# 5servoBreakoutSchematic.net
KiCad netlist of a schematic drawn in EAGLE
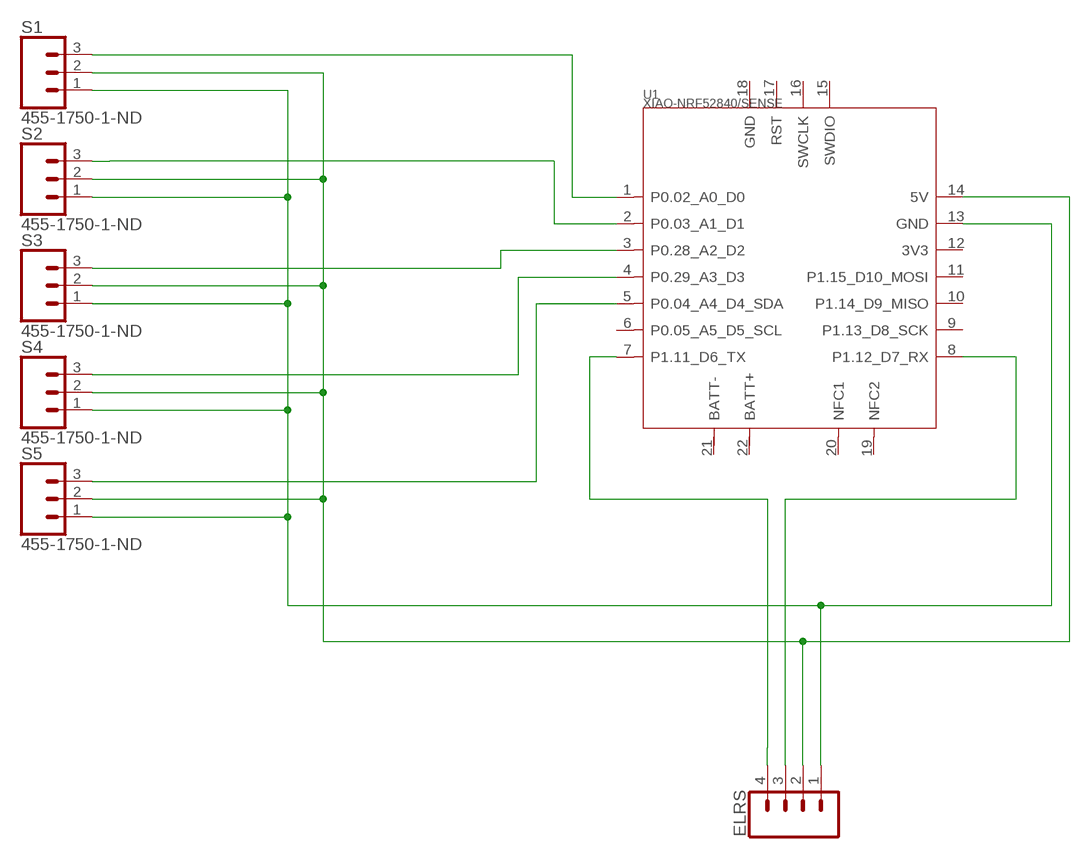
[diagram p0: schematic, sheet 1]

(export (version "E")
  (design (tool "Eeschema 10.0.6"))
  (components
    (comp (ref "ELRS")
      (value "CONN_04PTH")
      (footprint "eagle-import:1X04")
      (libsource (lib "eagle-import") (part "CONN_04PTH"))
    )
    (comp (ref "S1")
      (value "455-1750-1-ND")
      (footprint "eagle-import:1X03")
      (libsource (lib "eagle-import") (part "CONN_03"))
    )
    (comp (ref "S2")
      (value "455-1750-1-ND")
      (footprint "eagle-import:1X03")
      (libsource (lib "eagle-import") (part "CONN_03"))
    )
    (comp (ref "S3")
      (value "455-1750-1-ND")
      (footprint "eagle-import:1X03")
      (libsource (lib "eagle-import") (part "CONN_03"))
    )
    (comp (ref "S4")
      (value "455-1750-1-ND")
      (footprint "eagle-import:1X03")
      (libsource (lib "eagle-import") (part "CONN_03"))
    )
    (comp (ref "S5")
      (value "455-1750-1-ND")
      (footprint "eagle-import:1X03")
      (libsource (lib "eagle-import") (part "CONN_03"))
    )
    (comp (ref "U1")
      (value "XIAO-NRF52840/SENSE")
      (footprint "eagle-import:XIAO-NRF52840_SENSE-MODULE14P-2.54-21X17.8MM")
      (libsource (lib "eagle-import") (part "XIAO-NRF52840/SENSE"))
    )
  )
  (nets
    (net (code "1") (name "Net-(ELRS-Pad1)") (class "Default")
      (node (ref "ELRS") (pin "1") (pinfunction "1_1") (pintype "passive"))
      (node (ref "S1") (pin "1") (pinfunction "1_1") (pintype "passive"))
      (node (ref "S2") (pin "1") (pinfunction "1_1") (pintype "passive"))
      (node (ref "S3") (pin "1") (pinfunction "1_1") (pintype "passive"))
      (node (ref "S4") (pin "1") (pinfunction "1_1") (pintype "passive"))
      (node (ref "S5") (pin "1") (pinfunction "1_1") (pintype "passive"))
      (node (ref "U1") (pin "13") (pinfunction "GND_13") (pintype "bidirectional"))
    )
    (net (code "2") (name "Net-(U1-5V)") (class "Default")
      (node (ref "ELRS") (pin "2") (pinfunction "2_2") (pintype "passive"))
      (node (ref "S1") (pin "2") (pinfunction "2_2") (pintype "passive"))
      (node (ref "S2") (pin "2") (pinfunction "2_2") (pintype "passive"))
      (node (ref "S3") (pin "2") (pinfunction "2_2") (pintype "passive"))
      (node (ref "S4") (pin "2") (pinfunction "2_2") (pintype "passive"))
      (node (ref "S5") (pin "2") (pinfunction "2_2") (pintype "passive"))
      (node (ref "U1") (pin "14") (pinfunction "5V_14") (pintype "bidirectional"))
    )
    (net (code "3") (name "Net-(U1-P0.02_A0_D0)") (class "Default")
      (node (ref "S1") (pin "3") (pinfunction "3_3") (pintype "passive"))
      (node (ref "U1") (pin "1") (pinfunction "P0.02_A0_D0_1") (pintype "bidirectional"))
    )
    (net (code "4") (name "Net-(U1-P0.03_A1_D1)") (class "Default")
      (node (ref "S2") (pin "3") (pinfunction "3_3") (pintype "passive"))
      (node (ref "U1") (pin "2") (pinfunction "P0.03_A1_D1_2") (pintype "bidirectional"))
    )
    (net (code "5") (name "Net-(U1-P0.04_A4_D4_SDA)") (class "Default")
      (node (ref "S5") (pin "3") (pinfunction "3_3") (pintype "passive"))
      (node (ref "U1") (pin "5") (pinfunction "P0.04_A4_D4_SDA_5") (pintype "bidirectional"))
    )
    (net (code "6") (name "Net-(U1-P0.28_A2_D2)") (class "Default")
      (node (ref "S3") (pin "3") (pinfunction "3_3") (pintype "passive"))
      (node (ref "U1") (pin "3") (pinfunction "P0.28_A2_D2_3") (pintype "bidirectional"))
    )
    (net (code "7") (name "Net-(U1-P0.29_A3_D3)") (class "Default")
      (node (ref "S4") (pin "3") (pinfunction "3_3") (pintype "passive"))
      (node (ref "U1") (pin "4") (pinfunction "P0.29_A3_D3_4") (pintype "bidirectional"))
    )
    (net (code "8") (name "Net-(U1-P1.11_D6_TX)") (class "Default")
      (node (ref "ELRS") (pin "4") (pinfunction "4_4") (pintype "passive"))
      (node (ref "U1") (pin "7") (pinfunction "P1.11_D6_TX_7") (pintype "bidirectional"))
    )
    (net (code "9") (name "Net-(U1-P1.12_D7_RX)") (class "Default")
      (node (ref "ELRS") (pin "3") (pinfunction "3_3") (pintype "passive"))
      (node (ref "U1") (pin "8") (pinfunction "P1.12_D7_RX_8") (pintype "bidirectional"))
    )
    (net (code "10") (name "unconnected-(U1-3V3-Pad12)") (class "Default")
      (node (ref "U1") (pin "12") (pinfunction "3V3_12") (pintype "bidirectional"))
    )
    (net (code "11") (name "unconnected-(U1-BATT+-Pad22)") (class "Default")
      (node (ref "U1") (pin "22") (pinfunction "BATT+_22") (pintype "bidirectional"))
    )
    (net (code "12") (name "unconnected-(U1-BATT--Pad21)") (class "Default")
      (node (ref "U1") (pin "21") (pinfunction "BATT-_21") (pintype "bidirectional"))
    )
    (net (code "13") (name "unconnected-(U1-GND-Pad18)") (class "Default")
      (node (ref "U1") (pin "18") (pinfunction "GND_18") (pintype "bidirectional"))
    )
    (net (code "14") (name "unconnected-(U1-NFC1-Pad20)") (class "Default")
      (node (ref "U1") (pin "20") (pinfunction "NFC1_20") (pintype "bidirectional"))
    )
    (net (code "15") (name "unconnected-(U1-NFC2-Pad19)") (class "Default")
      (node (ref "U1") (pin "19") (pinfunction "NFC2_19") (pintype "bidirectional"))
    )
    (net (code "16") (name "unconnected-(U1-P0.05_A5_D5_SCL-Pad6)") (class "Default")
      (node (ref "U1") (pin "6") (pinfunction "P0.05_A5_D5_SCL_6") (pintype "bidirectional"))
    )
    (net (code "17") (name "unconnected-(U1-P1.13_D8_SCK-Pad9)") (class "Default")
      (node (ref "U1") (pin "9") (pinfunction "P1.13_D8_SCK_9") (pintype "bidirectional"))
    )
    (net (code "18") (name "unconnected-(U1-P1.14_D9_MISO-Pad10)") (class "Default")
      (node (ref "U1") (pin "10") (pinfunction "P1.14_D9_MISO_10") (pintype "bidirectional"))
    )
    (net (code "19") (name "unconnected-(U1-P1.15_D10_MOSI-Pad11)") (class "Default")
      (node (ref "U1") (pin "11") (pinfunction "P1.15_D10_MOSI_11") (pintype "bidirectional"))
    )
    (net (code "20") (name "unconnected-(U1-RST-Pad17)") (class "Default")
      (node (ref "U1") (pin "17") (pinfunction "RST_17") (pintype "bidirectional"))
    )
    (net (code "21") (name "unconnected-(U1-SWCLK-Pad16)") (class "Default")
      (node (ref "U1") (pin "16") (pinfunction "SWCLK_16") (pintype "bidirectional"))
    )
    (net (code "22") (name "unconnected-(U1-SWDIO-Pad15)") (class "Default")
      (node (ref "U1") (pin "15") (pinfunction "SWDIO_15") (pintype "bidirectional"))
    )
  )
)
